# Interface.net
KiCad netlist of a schematic drawn in Altium Designer
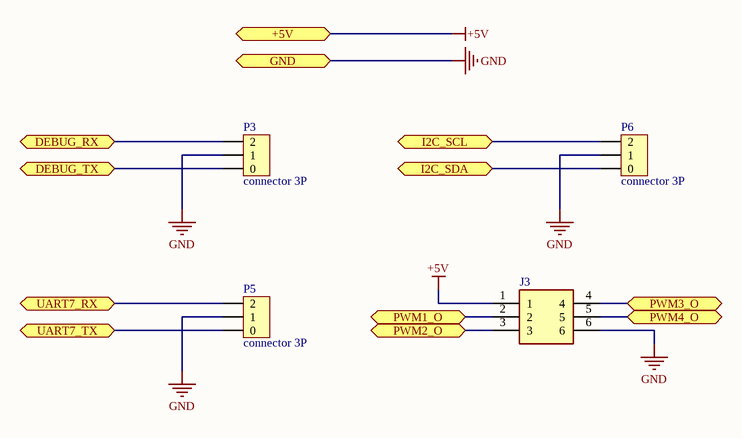
[diagram p0: Interface.SchDoc]

(export (version "E")
  (design (tool "Eeschema 10.0.6"))
  (components
    (comp (ref "J3")
      (value "SM06B-SRSS-TB__LF__SN_")
      (footprint "PCB1:SM06B-SRSS-TB")
      (description "Connector")
      (fields (field (name "MANUFACTURER_PART_NUMBER") "SM06B-SRSS-TB (LF)(SN)"))
      (libsource (lib "drone_RX_Project") (part "SM06B-SRSS-TB__LF__SN_"))
    )
    (comp (ref "P3")
      (value "connector 3P")
      (footprint "GH-3AB")
      (libsource (lib "Schlib_Trung") (part "connector 3P"))
    )
    (comp (ref "P5")
      (value "connector 3P")
      (footprint "GH-3AB")
      (libsource (lib "Schlib_Trung") (part "connector 3P"))
    )
    (comp (ref "P6")
      (value "connector 3P")
      (footprint "GH-3AB")
      (libsource (lib "Schlib_Trung") (part "connector 3P"))
    )
  )
  (nets
    (net (code "1") (name "+5V") (class "Default")
      (node (ref "J3") (pin "1") (pinfunction "1_1") (pintype "passive"))
    )
    (net (code "2") (name "/DEBUG_RX") (class "Default")
      (node (ref "P3") (pin "2") (pinfunction "2_2") (pintype "passive"))
    )
    (net (code "3") (name "/DEBUG_TX") (class "Default")
      (node (ref "P3") (pin "0") (pinfunction "0_0") (pintype "passive"))
    )
    (net (code "4") (name "/I2C_SCL") (class "Default")
      (node (ref "P6") (pin "2") (pinfunction "2_2") (pintype "passive"))
    )
    (net (code "5") (name "/I2C_SDA") (class "Default")
      (node (ref "P6") (pin "0") (pinfunction "0_0") (pintype "passive"))
    )
    (net (code "6") (name "/PWM1_O") (class "Default")
      (node (ref "J3") (pin "2") (pinfunction "2_2") (pintype "passive"))
    )
    (net (code "7") (name "/PWM2_O") (class "Default")
      (node (ref "J3") (pin "3") (pinfunction "3_3") (pintype "passive"))
    )
    (net (code "8") (name "/PWM3_O") (class "Default")
      (node (ref "J3") (pin "4") (pinfunction "4_4") (pintype "passive"))
    )
    (net (code "9") (name "/PWM4_O") (class "Default")
      (node (ref "J3") (pin "5") (pinfunction "5_5") (pintype "passive"))
    )
    (net (code "10") (name "/UART7_RX") (class "Default")
      (node (ref "P5") (pin "2") (pinfunction "2_2") (pintype "passive"))
    )
    (net (code "11") (name "/UART7_TX") (class "Default")
      (node (ref "P5") (pin "0") (pinfunction "0_0") (pintype "passive"))
    )
    (net (code "12") (name "GND") (class "Default")
      (node (ref "J3") (pin "6") (pinfunction "6_6") (pintype "passive"))
      (node (ref "P3") (pin "1") (pinfunction "1_1") (pintype "passive"))
      (node (ref "P5") (pin "1") (pinfunction "1_1") (pintype "passive"))
      (node (ref "P6") (pin "1") (pinfunction "1_1") (pintype "passive"))
    )
  )
)
